# A2D_ascii.net
KiCad netlist of a schematic drawn in Altium Designer
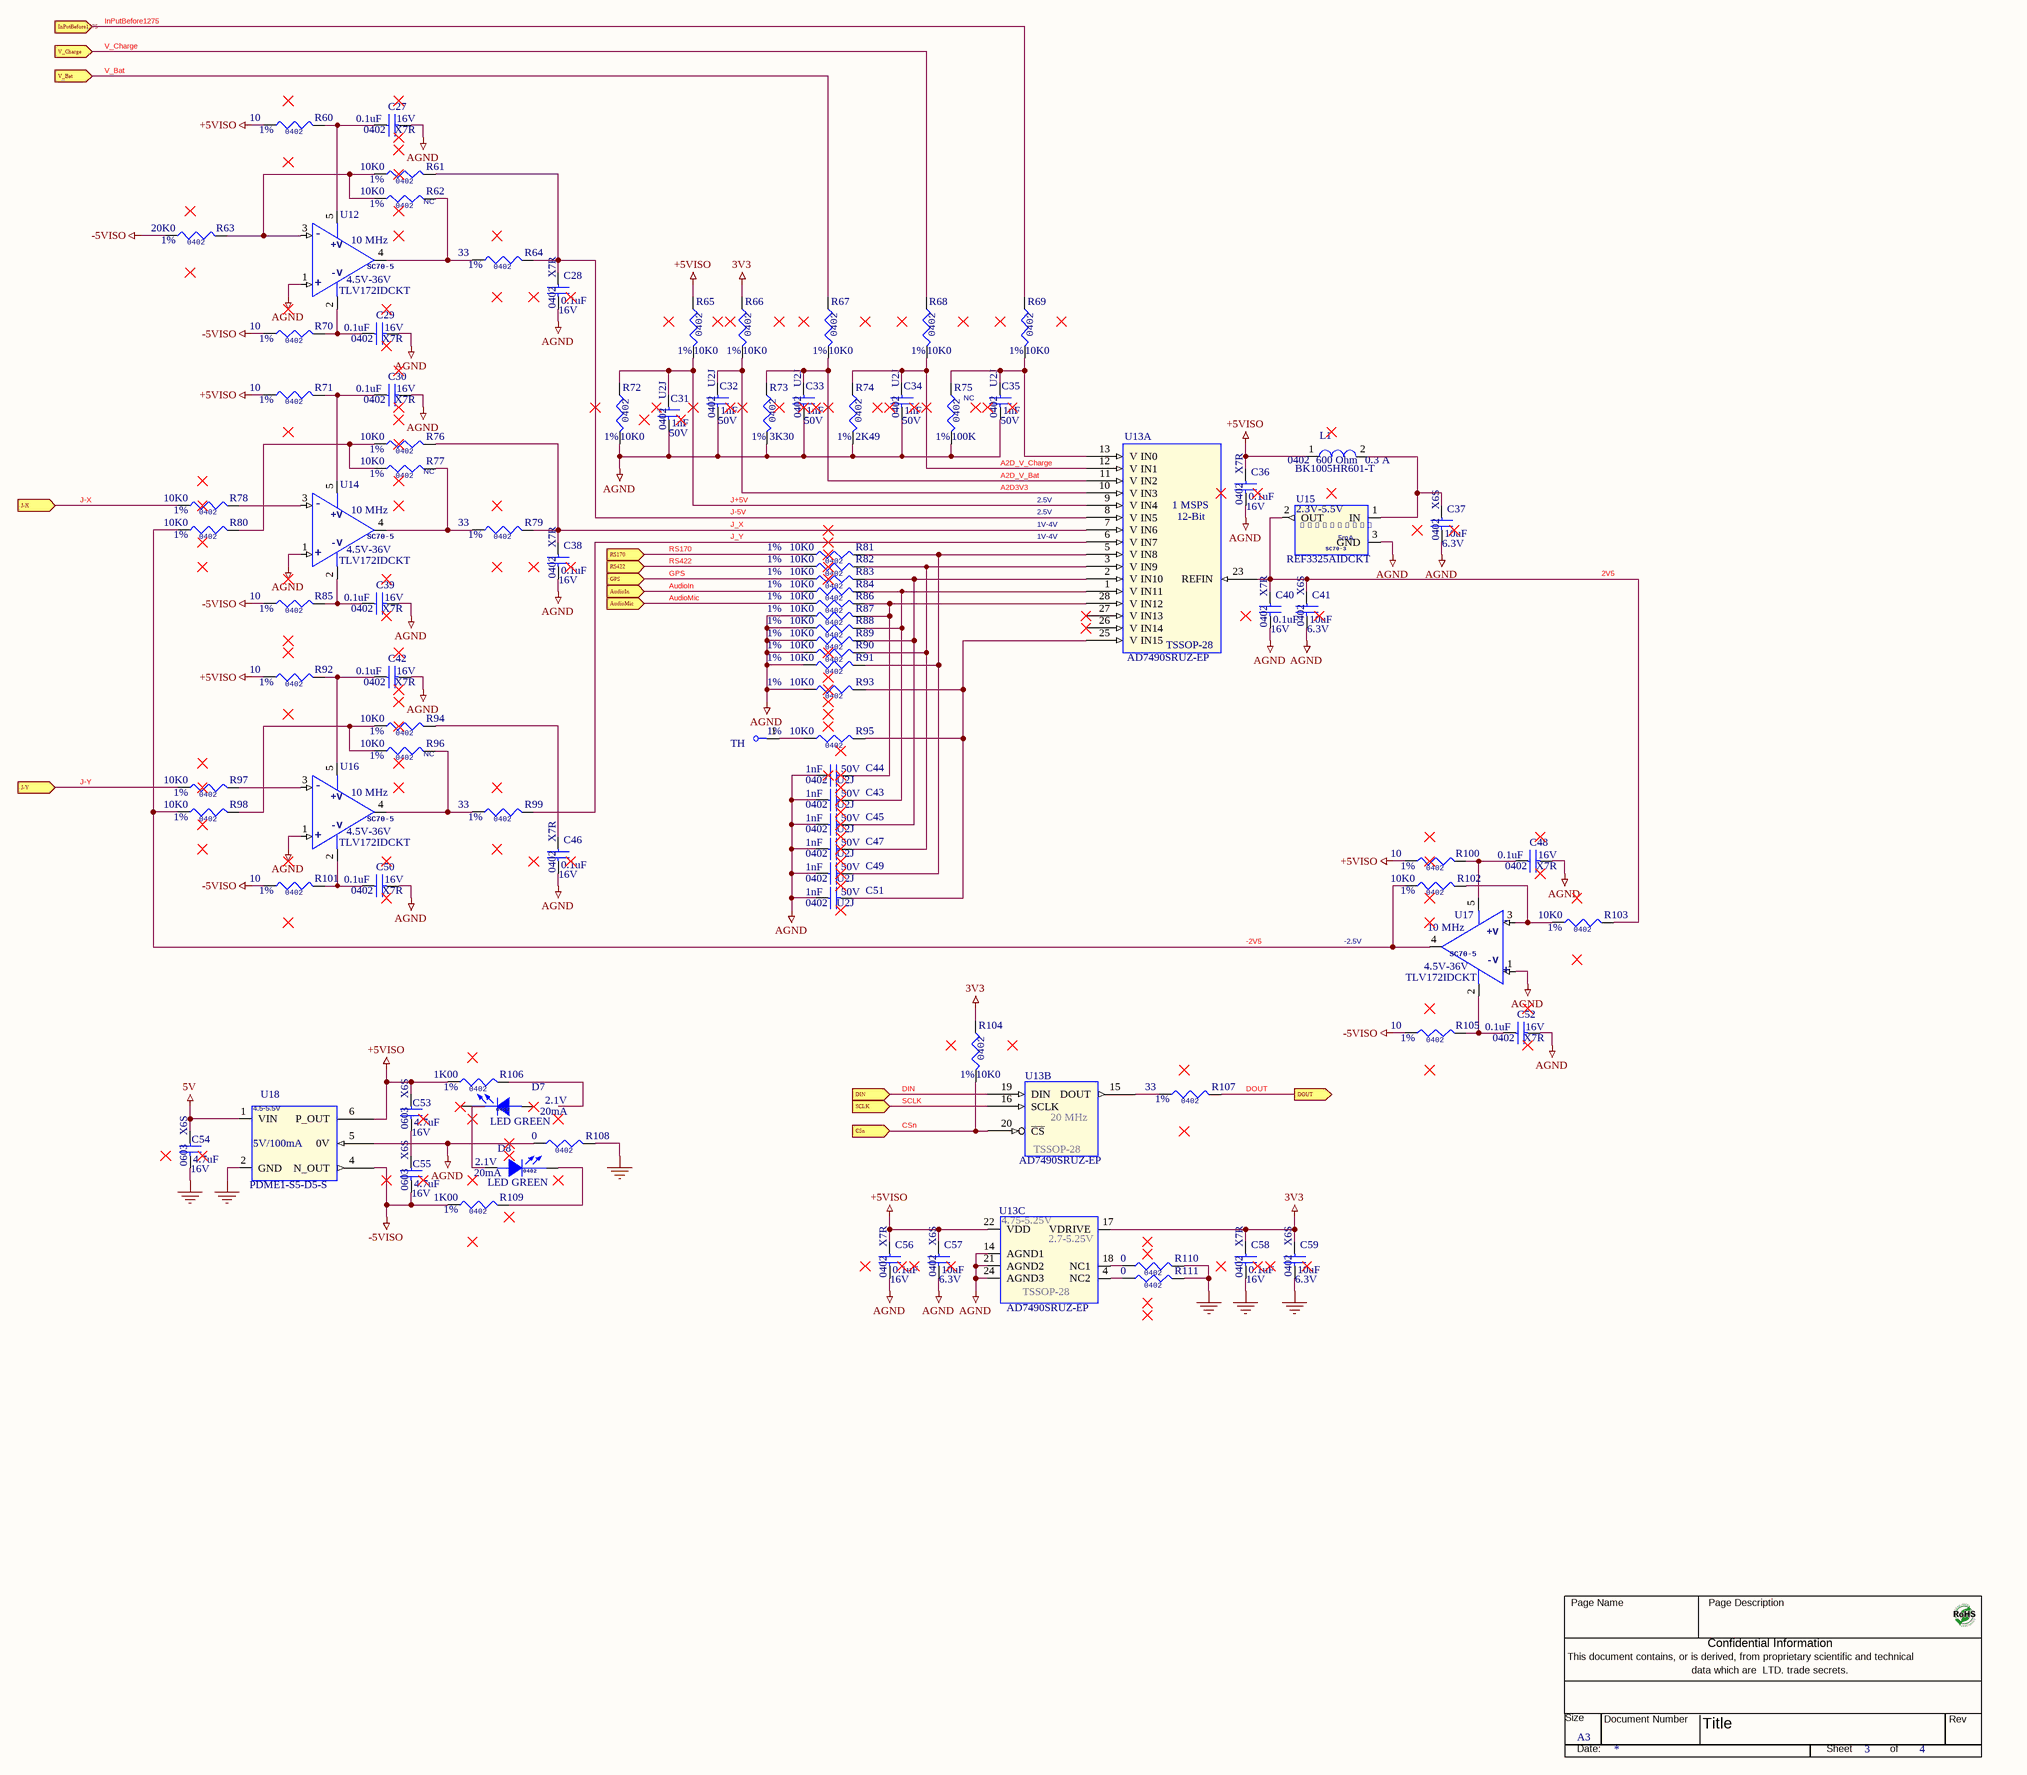
[diagram p0: A2D_ascii.SchDoc]

(export (version "E")
  (design (tool "Eeschema 10.0.6"))
  (components
    (comp (ref "*")
      (value "MobulusTitleBlockBlank")
      (fields
        (field (name "PAGE SIZE") "A3")
        (field (name "PAGE NUMBER") "3")
        (field (name "PAGE COUNT") "4")
      )
      (libsource (lib "*") (part "MobulusTitleBlockBlank"))
    )
    (comp (ref "C27")
      (value "0.1uF")
      (footprint "0402")
      (description "CAP_CER_0.1uF_16V_X7R_0402")
      (fields
        (field (name "VOLTAGE") "16V")
        (field (name "PART NUMBER") "CC0402KRX7R7BB104")
        (field (name "PCBFOOTPRINT") "0402   X7R")
        (field (name "MFG") "Yageo")
      )
      (libsource (lib "*") (part "CAP0402_0.1uF 16V"))
    )
    (comp (ref "C28")
      (value "0.1uF")
      (footprint "0402")
      (description "CAP_CER_0.1uF_16V_X7R_0402")
      (fields
        (field (name "VOLTAGE") "16V")
        (field (name "PART NUMBER") "CC0402KRX7R7BB104")
        (field (name "PCBFOOTPRINT") "0402   X7R")
        (field (name "MFG") "Yageo")
      )
      (libsource (lib "") (part "CAP0402_0.1uF 16V_1"))
    )
    (comp (ref "C29")
      (value "0.1uF")
      (footprint "0402")
      (description "CAP_CER_0.1uF_16V_X7R_0402")
      (fields
        (field (name "VOLTAGE") "16V")
        (field (name "PART NUMBER") "CC0402KRX7R7BB104")
        (field (name "PCBFOOTPRINT") "0402   X7R")
        (field (name "MFG") "Yageo")
      )
      (libsource (lib "*") (part "CAP0402_0.1uF 16V"))
    )
    (comp (ref "C30")
      (value "0.1uF")
      (footprint "0402")
      (description "CAP_CER_0.1uF_16V_X7R_0402")
      (fields
        (field (name "VOLTAGE") "16V")
        (field (name "PART NUMBER") "CC0402KRX7R7BB104")
        (field (name "PCBFOOTPRINT") "0402   X7R")
        (field (name "MFG") "Yageo")
      )
      (libsource (lib "*") (part "CAP0402_0.1uF 16V"))
    )
    (comp (ref "C31")
      (value "1nF")
      (footprint "0402")
      (description "CAP_CER_1nF_50V_0402_U2J")
      (fields
        (field (name "VOLTAGE") "50V")
        (field (name "PART NUMBER") "C0402C102J5JAC7867")
        (field (name "PCBFOOTPRINT") "0402   U2J")
        (field (name "MFG") "KEMET")
      )
      (libsource (lib "*") (part "CAP0402_1nF 50V"))
    )
    (comp (ref "C32")
      (value "1nF")
      (footprint "0402")
      (description "CAP_CER_1nF_50V_0402_U2J")
      (fields
        (field (name "VOLTAGE") "50V")
        (field (name "PART NUMBER") "C0402C102J5JAC7867")
        (field (name "PCBFOOTPRINT") "0402   U2J")
        (field (name "MFG") "KEMET")
      )
      (libsource (lib "*") (part "CAP0402_1nF 50V"))
    )
    (comp (ref "C33")
      (value "1nF")
      (footprint "0402")
      (description "CAP_CER_1nF_50V_0402_U2J")
      (fields
        (field (name "VOLTAGE") "50V")
        (field (name "PART NUMBER") "C0402C102J5JAC7867")
        (field (name "PCBFOOTPRINT") "0402   U2J")
        (field (name "MFG") "KEMET")
      )
      (libsource (lib "*") (part "CAP0402_1nF 50V"))
    )
    (comp (ref "C34")
      (value "1nF")
      (footprint "0402")
      (description "CAP_CER_1nF_50V_0402_U2J")
      (fields
        (field (name "VOLTAGE") "50V")
        (field (name "PART NUMBER") "C0402C102J5JAC7867")
        (field (name "PCBFOOTPRINT") "0402   U2J")
        (field (name "MFG") "KEMET")
      )
      (libsource (lib "*") (part "CAP0402_1nF 50V"))
    )
    (comp (ref "C35")
      (value "1nF")
      (footprint "0402")
      (description "CAP_CER_1nF_50V_0402_U2J")
      (fields
        (field (name "VOLTAGE") "50V")
        (field (name "PART NUMBER") "C0402C102J5JAC7867")
        (field (name "PCBFOOTPRINT") "0402   U2J")
        (field (name "MFG") "KEMET")
      )
      (libsource (lib "*") (part "CAP0402_1nF 50V"))
    )
    (comp (ref "C36")
      (value "0.1uF")
      (footprint "0402")
      (description "CAP_CER_0.1uF_16V_X7R_0402")
      (fields
        (field (name "VOLTAGE") "16V")
        (field (name "PART NUMBER") "CC0402KRX7R7BB104")
        (field (name "PCBFOOTPRINT") "0402   X7R")
        (field (name "MFG") "Yageo")
      )
      (libsource (lib "") (part "CAP0402_0.1uF 16V_1"))
    )
    (comp (ref "C37")
      (value "10uF")
      (footprint "0402")
      (description "CAP CER 10UF 6.3V X6S 0402")
      (fields
        (field (name "VOLTAGE") "6.3V")
        (field (name "PART NUMBER") "GRM155C80J106ME11J")
        (field (name "PCBFOOTPRINT") "0402   X6S")
        (field (name "MFG") "Murata Electronics")
      )
      (libsource (lib "*") (part "CAP0402_10uF 6.3V"))
    )
    (comp (ref "C38")
      (value "0.1uF")
      (footprint "0402")
      (description "CAP_CER_0.1uF_16V_X7R_0402")
      (fields
        (field (name "VOLTAGE") "16V")
        (field (name "PART NUMBER") "CC0402KRX7R7BB104")
        (field (name "PCBFOOTPRINT") "0402   X7R")
        (field (name "MFG") "Yageo")
      )
      (libsource (lib "") (part "CAP0402_0.1uF 16V_1"))
    )
    (comp (ref "C39")
      (value "0.1uF")
      (footprint "0402")
      (description "CAP_CER_0.1uF_16V_X7R_0402")
      (fields
        (field (name "VOLTAGE") "16V")
        (field (name "PART NUMBER") "CC0402KRX7R7BB104")
        (field (name "PCBFOOTPRINT") "0402   X7R")
        (field (name "MFG") "Yageo")
      )
      (libsource (lib "*") (part "CAP0402_0.1uF 16V"))
    )
    (comp (ref "C40")
      (value "0.1uF")
      (footprint "0402")
      (description "CAP_CER_0.1uF_16V_X7R_0402")
      (fields
        (field (name "VOLTAGE") "16V")
        (field (name "PART NUMBER") "CC0402KRX7R7BB104")
        (field (name "PCBFOOTPRINT") "0402   X7R")
        (field (name "MFG") "Yageo")
      )
      (libsource (lib "") (part "CAP0402_0.1uF 16V_1"))
    )
    (comp (ref "C41")
      (value "10uF")
      (footprint "0402")
      (description "CAP CER 10UF 6.3V X6S 0402")
      (fields
        (field (name "VOLTAGE") "6.3V")
        (field (name "PART NUMBER") "GRM155C80J106ME11J")
        (field (name "PCBFOOTPRINT") "0402   X6S")
        (field (name "MFG") "Murata Electronics")
      )
      (libsource (lib "*") (part "CAP0402_10uF 6.3V"))
    )
    (comp (ref "C42")
      (value "0.1uF")
      (footprint "0402")
      (description "CAP_CER_0.1uF_16V_X7R_0402")
      (fields
        (field (name "VOLTAGE") "16V")
        (field (name "PART NUMBER") "CC0402KRX7R7BB104")
        (field (name "PCBFOOTPRINT") "0402   X7R")
        (field (name "MFG") "Yageo")
      )
      (libsource (lib "*") (part "CAP0402_0.1uF 16V"))
    )
    (comp (ref "C43")
      (value "1nF")
      (footprint "0402")
      (description "CAP_CER_1nF_50V_0402_U2J")
      (fields
        (field (name "VOLTAGE") "50V")
        (field (name "PART NUMBER") "C0402C102J5JAC7867")
        (field (name "PCBFOOTPRINT") "0402   U2J")
        (field (name "MFG") "KEMET")
      )
      (libsource (lib "") (part "CAP0402_1nF 50V_1"))
    )
    (comp (ref "C44")
      (value "1nF")
      (footprint "0402")
      (description "CAP_CER_1nF_50V_0402_U2J")
      (fields
        (field (name "VOLTAGE") "50V")
        (field (name "PART NUMBER") "C0402C102J5JAC7867")
        (field (name "PCBFOOTPRINT") "0402   U2J")
        (field (name "MFG") "KEMET")
      )
      (libsource (lib "") (part "CAP0402_1nF 50V_1"))
    )
    (comp (ref "C45")
      (value "1nF")
      (footprint "0402")
      (description "CAP_CER_1nF_50V_0402_U2J")
      (fields
        (field (name "VOLTAGE") "50V")
        (field (name "PART NUMBER") "C0402C102J5JAC7867")
        (field (name "PCBFOOTPRINT") "0402   U2J")
        (field (name "MFG") "KEMET")
      )
      (libsource (lib "") (part "CAP0402_1nF 50V_1"))
    )
    (comp (ref "C46")
      (value "0.1uF")
      (footprint "0402")
      (description "CAP_CER_0.1uF_16V_X7R_0402")
      (fields
        (field (name "VOLTAGE") "16V")
        (field (name "PART NUMBER") "CC0402KRX7R7BB104")
        (field (name "PCBFOOTPRINT") "0402   X7R")
        (field (name "MFG") "Yageo")
      )
      (libsource (lib "") (part "CAP0402_0.1uF 16V_1"))
    )
    (comp (ref "C47")
      (value "1nF")
      (footprint "0402")
      (description "CAP_CER_1nF_50V_0402_U2J")
      (fields
        (field (name "VOLTAGE") "50V")
        (field (name "PART NUMBER") "C0402C102J5JAC7867")
        (field (name "PCBFOOTPRINT") "0402   U2J")
        (field (name "MFG") "KEMET")
      )
      (libsource (lib "") (part "CAP0402_1nF 50V_1"))
    )
    (comp (ref "C48")
      (value "0.1uF")
      (footprint "0402")
      (description "CAP_CER_0.1uF_16V_X7R_0402")
      (fields
        (field (name "VOLTAGE") "16V")
        (field (name "PART NUMBER") "CC0402KRX7R7BB104")
        (field (name "PCBFOOTPRINT") "0402   X7R")
        (field (name "MFG") "Yageo")
      )
      (libsource (lib "*") (part "CAP0402_0.1uF 16V"))
    )
    (comp (ref "C49")
      (value "1nF")
      (footprint "0402")
      (description "CAP_CER_1nF_50V_0402_U2J")
      (fields
        (field (name "VOLTAGE") "50V")
        (field (name "PART NUMBER") "C0402C102J5JAC7867")
        (field (name "PCBFOOTPRINT") "0402   U2J")
        (field (name "MFG") "KEMET")
      )
      (libsource (lib "") (part "CAP0402_1nF 50V_1"))
    )
    (comp (ref "C50")
      (value "0.1uF")
      (footprint "0402")
      (description "CAP_CER_0.1uF_16V_X7R_0402")
      (fields
        (field (name "VOLTAGE") "16V")
        (field (name "PART NUMBER") "CC0402KRX7R7BB104")
        (field (name "PCBFOOTPRINT") "0402   X7R")
        (field (name "MFG") "Yageo")
      )
      (libsource (lib "*") (part "CAP0402_0.1uF 16V"))
    )
    (comp (ref "C51")
      (value "1nF")
      (footprint "0402")
      (description "CAP_CER_1nF_50V_0402_U2J")
      (fields
        (field (name "VOLTAGE") "50V")
        (field (name "PART NUMBER") "C0402C102J5JAC7867")
        (field (name "PCBFOOTPRINT") "0402   U2J")
        (field (name "MFG") "KEMET")
      )
      (libsource (lib "") (part "CAP0402_1nF 50V_1"))
    )
    (comp (ref "C52")
      (value "0.1uF")
      (footprint "0402")
      (description "CAP_CER_0.1uF_16V_X7R_0402")
      (fields
        (field (name "VOLTAGE") "16V")
        (field (name "PART NUMBER") "CC0402KRX7R7BB104")
        (field (name "PCBFOOTPRINT") "0402   X7R")
        (field (name "MFG") "Yageo")
      )
      (libsource (lib "*") (part "CAP0402_0.1uF 16V"))
    )
    (comp (ref "C53")
      (value "4.7uF")
      (footprint "0603")
      (description "CAP_CER_4.7UF_16V_X6S_0603")
      (fields
        (field (name "VOLTAGE") "16V")
        (field (name "PART NUMBER") "C1608X6S1C475M080AC")
        (field (name "PCBFOOTPRINT") "0603   X6S")
        (field (name "MFG") "TDK Corporation")
      )
      (libsource (lib "*") (part "CAP0603_4.7uF 16V"))
    )
    (comp (ref "C54")
      (value "4.7uF")
      (footprint "0603")
      (description "CAP_CER_4.7UF_16V_X6S_0603")
      (fields
        (field (name "VOLTAGE") "16V")
        (field (name "PART NUMBER") "C1608X6S1C475M080AC")
        (field (name "PCBFOOTPRINT") "0603   X6S")
        (field (name "MFG") "TDK Corporation")
      )
      (libsource (lib "*") (part "CAP0603_4.7uF 16V"))
    )
    (comp (ref "C55")
      (value "4.7uF")
      (footprint "0603")
      (description "CAP_CER_4.7UF_16V_X6S_0603")
      (fields
        (field (name "VOLTAGE") "16V")
        (field (name "PART NUMBER") "C1608X6S1C475M080AC")
        (field (name "PCBFOOTPRINT") "0603   X6S")
        (field (name "MFG") "TDK Corporation")
      )
      (libsource (lib "*") (part "CAP0603_4.7uF 16V"))
    )
    (comp (ref "C56")
      (value "0.1uF")
      (footprint "0402")
      (description "CAP_CER_0.1uF_16V_X7R_0402")
      (fields
        (field (name "VOLTAGE") "16V")
        (field (name "PART NUMBER") "CC0402KRX7R7BB104")
        (field (name "PCBFOOTPRINT") "0402   X7R")
        (field (name "MFG") "Yageo")
      )
      (libsource (lib "") (part "CAP0402_0.1uF 16V_1"))
    )
    (comp (ref "C57")
      (value "10uF")
      (footprint "0402")
      (description "CAP CER 10UF 6.3V X6S 0402")
      (fields
        (field (name "VOLTAGE") "6.3V")
        (field (name "PART NUMBER") "GRM155C80J106ME11J")
        (field (name "PCBFOOTPRINT") "0402   X6S")
        (field (name "MFG") "Murata Electronics")
      )
      (libsource (lib "*") (part "CAP0402_10uF 6.3V"))
    )
    (comp (ref "C58")
      (value "0.1uF")
      (footprint "0402")
      (description "CAP_CER_0.1uF_16V_X7R_0402")
      (fields
        (field (name "VOLTAGE") "16V")
        (field (name "PART NUMBER") "CC0402KRX7R7BB104")
        (field (name "PCBFOOTPRINT") "0402   X7R")
        (field (name "MFG") "Yageo")
      )
      (libsource (lib "") (part "CAP0402_0.1uF 16V_1"))
    )
    (comp (ref "C59")
      (value "10uF")
      (footprint "0402")
      (description "CAP CER 10UF 6.3V X6S 0402")
      (fields
        (field (name "VOLTAGE") "6.3V")
        (field (name "PART NUMBER") "GRM155C80J106ME11J")
        (field (name "PCBFOOTPRINT") "0402   X6S")
        (field (name "MFG") "Murata Electronics")
      )
      (libsource (lib "*") (part "CAP0402_10uF 6.3V"))
    )
    (comp (ref "D7")
      (value "LED GREEN")
      (footprint "LED_0402")
      (description "LED GREEN CLEAR CHIP SMD")
      (fields
        (field (name "VOLTAGE") "2.1V")
        (field (name "PART NUMBER") "XZVG68W-2")
        (field (name "MFG") "SunLED")
        (field (name "CURRENT") "20mA")
      )
      (libsource (lib "*") (part "LED_0402_GREEN"))
    )
    (comp (ref "D8")
      (value "LED GREEN")
      (footprint "LED_0402")
      (description "LED GREEN CLEAR CHIP SMD")
      (fields
        (field (name "VOLTAGE") "2.1V")
        (field (name "PART NUMBER") "XZVG68W-2")
        (field (name "MFG") "SunLED")
        (field (name "CURRENT") "20mA")
      )
      (libsource (lib "*") (part "LED_0402_GREEN"))
    )
    (comp (ref "ICT1") (value "TH") (footprint "ICT") (libsource (lib "*") (part "ICT")))
    (comp (ref "L1")
      (value "BK1005HR601-T")
      (footprint "L0402")
      (description "FERRITE BEAD 600 OHM 0402 1LN")
      (fields
        (field (name "IMPEDANCE") "600 Ohm")
        (field (name "PCBFOOTPRINT") "0402")
        (field (name "MFG") "Taiyo Yuden")
        (field (name "CURRENT") "0.3 A")
      )
      (libsource (lib "*") (part "BK1005HR601-T 600 0.3A"))
    )
    (comp (ref "R60")
      (value "10")
      (footprint "0402")
      (description "RES SMD 10 OHM 1% 1/16W 0402")
      (fields
        (field (name "TOLERANCE") "1%")
        (field (name "POWER") "1/16W")
        (field (name "PART NUMBER") "RC0402FR-0710RL")
      )
      (libsource (lib "*") (part "R0402_10R_1%"))
    )
    (comp (ref "R61")
      (value "10K0")
      (footprint "0402")
      (description "RES SMD 10K OHM 1% 1/16W 0402")
      (fields
        (field (name "TOLERANCE") "1%")
        (field (name "POWER") "1/16W")
        (field (name "PART NUMBER") "RC0402FR-0710KL")
      )
      (libsource (lib "*") (part "R0402_10K0_1%"))
    )
    (comp (ref "R62")
      (value "10K0")
      (footprint "0402")
      (description "RES SMD 10K OHM 1% 1/16W 0402")
      (fields
        (field (name "TOLERANCE") "1%")
        (field (name "POWER") "1/16W")
        (field (name "PART NUMBER") "RC0402FR-0710KL")
        (field (name "ASSY") "NC")
      )
      (libsource (lib "*") (part "R0402_10K0_1%"))
    )
    (comp (ref "R63")
      (value "20K0")
      (footprint "0402")
      (description "RES SMD 20K OHM 1% 1/16W 0402")
      (fields
        (field (name "TOLERANCE") "1%")
        (field (name "POWER") "1/16W")
        (field (name "PART NUMBER") "RC0402FR-0720KL")
      )
      (libsource (lib "*") (part "R0402_20K0_1%"))
    )
    (comp (ref "R64")
      (value "33")
      (footprint "0402")
      (description "RES 33R 1% 1/5W 0402")
      (fields
        (field (name "TOLERANCE") "1%")
        (field (name "POWER") "1/16W")
        (field (name "PART NUMBER") "RCS040233R0FKED")
      )
      (libsource (lib "*") (part "R0402_33R_1%"))
    )
    (comp (ref "R65")
      (value "10K0")
      (footprint "0402")
      (description "RES SMD 10K OHM 1% 1/16W 0402")
      (fields
        (field (name "TOLERANCE") "1%")
        (field (name "POWER") "1/16W")
        (field (name "PART NUMBER") "RC0402FR-0710KL")
      )
      (libsource (lib "") (part "R0402_10K0_1%_1"))
    )
    (comp (ref "R66")
      (value "10K0")
      (footprint "0402")
      (description "RES SMD 10K OHM 1% 1/16W 0402")
      (fields
        (field (name "TOLERANCE") "1%")
        (field (name "POWER") "1/16W")
        (field (name "PART NUMBER") "RC0402FR-0710KL")
      )
      (libsource (lib "") (part "R0402_10K0_1%_1"))
    )
    (comp (ref "R67")
      (value "10K0")
      (footprint "0402")
      (description "RES SMD 10K OHM 1% 1/16W 0402")
      (fields
        (field (name "TOLERANCE") "1%")
        (field (name "POWER") "1/16W")
        (field (name "PART NUMBER") "RC0402FR-0710KL")
      )
      (libsource (lib "") (part "R0402_10K0_1%_1"))
    )
    (comp (ref "R68")
      (value "10K0")
      (footprint "0402")
      (description "RES SMD 10K OHM 1% 1/16W 0402")
      (fields
        (field (name "TOLERANCE") "1%")
        (field (name "POWER") "1/16W")
        (field (name "PART NUMBER") "RC0402FR-0710KL")
      )
      (libsource (lib "") (part "R0402_10K0_1%_1"))
    )
    (comp (ref "R69")
      (value "10K0")
      (footprint "0402")
      (description "RES SMD 10K OHM 1% 1/16W 0402")
      (fields
        (field (name "TOLERANCE") "1%")
        (field (name "POWER") "1/16W")
        (field (name "PART NUMBER") "RC0402FR-0710KL")
      )
      (libsource (lib "") (part "R0402_10K0_1%_1"))
    )
    (comp (ref "R70")
      (value "10")
      (footprint "0402")
      (description "RES SMD 10 OHM 1% 1/16W 0402")
      (fields
        (field (name "TOLERANCE") "1%")
        (field (name "POWER") "1/16W")
        (field (name "PART NUMBER") "RC0402FR-0710RL")
      )
      (libsource (lib "*") (part "R0402_10R_1%"))
    )
    (comp (ref "R71")
      (value "10")
      (footprint "0402")
      (description "RES SMD 10 OHM 1% 1/16W 0402")
      (fields
        (field (name "TOLERANCE") "1%")
        (field (name "POWER") "1/16W")
        (field (name "PART NUMBER") "RC0402FR-0710RL")
      )
      (libsource (lib "*") (part "R0402_10R_1%"))
    )
    (comp (ref "R72")
      (value "10K0")
      (footprint "0402")
      (description "RES SMD 10K OHM 1% 1/16W 0402")
      (fields
        (field (name "TOLERANCE") "1%")
        (field (name "POWER") "1/16W")
        (field (name "PART NUMBER") "RC0402FR-0710KL")
      )
      (libsource (lib "") (part "R0402_10K0_1%_1"))
    )
    (comp (ref "R73")
      (value "3K30")
      (footprint "0402")
      (description "RES 3K3 1% 1/16W 0402")
      (fields
        (field (name "TOLERANCE") "1%")
        (field (name "POWER") "1/16W")
        (field (name "PART NUMBER") "RT0402FRE073K3L")
      )
      (libsource (lib "*") (part "R0402_3K30_1%"))
    )
    (comp (ref "R74")
      (value "2K49")
      (footprint "0402")
      (description "RES 2K49 1% 1/16W 0402")
      (fields
        (field (name "TOLERANCE") "1%")
        (field (name "POWER") "1/16W")
        (field (name "PART NUMBER") "RC0402FR-072K49L")
      )
      (libsource (lib "*") (part "R0402_2K49_1%"))
    )
    (comp (ref "R75")
      (value "100K")
      (footprint "0402")
      (description "RES SMD 100K OHM 1% 1/16W 0402")
      (fields
        (field (name "TOLERANCE") "1%")
        (field (name "POWER") "1/16W")
        (field (name "PART NUMBER") "RC0402FR-07100KL")
        (field (name "ASSY") "NC")
      )
      (libsource (lib "*") (part "R0402_100K_1%"))
    )
    (comp (ref "R76")
      (value "10K0")
      (footprint "0402")
      (description "RES SMD 10K OHM 1% 1/16W 0402")
      (fields
        (field (name "TOLERANCE") "1%")
        (field (name "POWER") "1/16W")
        (field (name "PART NUMBER") "RC0402FR-0710KL")
      )
      (libsource (lib "*") (part "R0402_10K0_1%"))
    )
    (comp (ref "R77")
      (value "10K0")
      (footprint "0402")
      (description "RES SMD 10K OHM 1% 1/16W 0402")
      (fields
        (field (name "TOLERANCE") "1%")
        (field (name "POWER") "1/16W")
        (field (name "PART NUMBER") "RC0402FR-0710KL")
        (field (name "ASSY") "NC")
      )
      (libsource (lib "*") (part "R0402_10K0_1%"))
    )
    (comp (ref "R78")
      (value "10K0")
      (footprint "0402")
      (description "RES SMD 10K OHM 1% 1/16W 0402")
      (fields
        (field (name "TOLERANCE") "1%")
        (field (name "POWER") "1/16W")
        (field (name "PART NUMBER") "RC0402FR-0710KL")
      )
      (libsource (lib "*") (part "R0402_10K0_1%"))
    )
    (comp (ref "R79")
      (value "33")
      (footprint "0402")
      (description "RES 33R 1% 1/5W 0402")
      (fields
        (field (name "TOLERANCE") "1%")
        (field (name "POWER") "1/16W")
        (field (name "PART NUMBER") "RCS040233R0FKED")
      )
      (libsource (lib "*") (part "R0402_33R_1%"))
    )
    (comp (ref "R80")
      (value "10K0")
      (footprint "0402")
      (description "RES SMD 10K OHM 1% 1/16W 0402")
      (fields
        (field (name "TOLERANCE") "1%")
        (field (name "POWER") "1/16W")
        (field (name "PART NUMBER") "RC0402FR-0710KL")
      )
      (libsource (lib "*") (part "R0402_10K0_1%"))
    )
    (comp (ref "R81")
      (value "10K0")
      (footprint "0402")
      (description "RES SMD 10K OHM 1% 1/16W 0402")
      (fields
        (field (name "TOLERANCE") "1%")
        (field (name "POWER") "1/16W")
        (field (name "PART NUMBER") "RC0402FR-0710KL")
      )
      (libsource (lib "*") (part "R0402_10K0_1%"))
    )
    (comp (ref "R82")
      (value "10K0")
      (footprint "0402")
      (description "RES SMD 10K OHM 1% 1/16W 0402")
      (fields
        (field (name "TOLERANCE") "1%")
        (field (name "POWER") "1/16W")
        (field (name "PART NUMBER") "RC0402FR-0710KL")
      )
      (libsource (lib "*") (part "R0402_10K0_1%"))
    )
    (comp (ref "R83")
      (value "10K0")
      (footprint "0402")
      (description "RES SMD 10K OHM 1% 1/16W 0402")
      (fields
        (field (name "TOLERANCE") "1%")
        (field (name "POWER") "1/16W")
        (field (name "PART NUMBER") "RC0402FR-0710KL")
      )
      (libsource (lib "*") (part "R0402_10K0_1%"))
    )
    (comp (ref "R84")
      (value "10K0")
      (footprint "0402")
      (description "RES SMD 10K OHM 1% 1/16W 0402")
      (fields
        (field (name "TOLERANCE") "1%")
        (field (name "POWER") "1/16W")
        (field (name "PART NUMBER") "RC0402FR-0710KL")
      )
      (libsource (lib "*") (part "R0402_10K0_1%"))
    )
    (comp (ref "R85")
      (value "10")
      (footprint "0402")
      (description "RES SMD 10 OHM 1% 1/16W 0402")
      (fields
        (field (name "TOLERANCE") "1%")
        (field (name "POWER") "1/16W")
        (field (name "PART NUMBER") "RC0402FR-0710RL")
      )
      (libsource (lib "*") (part "R0402_10R_1%"))
    )
    (comp (ref "R86")
      (value "10K0")
      (footprint "0402")
      (description "RES SMD 10K OHM 1% 1/16W 0402")
      (fields
        (field (name "TOLERANCE") "1%")
        (field (name "POWER") "1/16W")
        (field (name "PART NUMBER") "RC0402FR-0710KL")
      )
      (libsource (lib "*") (part "R0402_10K0_1%"))
    )
    (comp (ref "R87")
      (value "10K0")
      (footprint "0402")
      (description "RES SMD 10K OHM 1% 1/16W 0402")
      (fields
        (field (name "TOLERANCE") "1%")
        (field (name "POWER") "1/16W")
        (field (name "PART NUMBER") "RC0402FR-0710KL")
      )
      (libsource (lib "*") (part "R0402_10K0_1%"))
    )
    (comp (ref "R88")
      (value "10K0")
      (footprint "0402")
      (description "RES SMD 10K OHM 1% 1/16W 0402")
      (fields
        (field (name "TOLERANCE") "1%")
        (field (name "POWER") "1/16W")
        (field (name "PART NUMBER") "RC0402FR-0710KL")
      )
      (libsource (lib "*") (part "R0402_10K0_1%"))
    )
    (comp (ref "R89")
      (value "10K0")
      (footprint "0402")
      (description "RES SMD 10K OHM 1% 1/16W 0402")
      (fields
        (field (name "TOLERANCE") "1%")
        (field (name "POWER") "1/16W")
        (field (name "PART NUMBER") "RC0402FR-0710KL")
      )
      (libsource (lib "*") (part "R0402_10K0_1%"))
    )
    (comp (ref "R90")
      (value "10K0")
      (footprint "0402")
      (description "RES SMD 10K OHM 1% 1/16W 0402")
      (fields
        (field (name "TOLERANCE") "1%")
        (field (name "POWER") "1/16W")
        (field (name "PART NUMBER") "RC0402FR-0710KL")
      )
      (libsource (lib "*") (part "R0402_10K0_1%"))
    )
    (comp (ref "R91")
      (value "10K0")
      (footprint "0402")
      (description "RES SMD 10K OHM 1% 1/16W 0402")
      (fields
        (field (name "TOLERANCE") "1%")
        (field (name "POWER") "1/16W")
        (field (name "PART NUMBER") "RC0402FR-0710KL")
      )
      (libsource (lib "*") (part "R0402_10K0_1%"))
    )
    (comp (ref "R92")
      (value "10")
      (footprint "0402")
      (description "RES SMD 10 OHM 1% 1/16W 0402")
      (fields
        (field (name "TOLERANCE") "1%")
        (field (name "POWER") "1/16W")
        (field (name "PART NUMBER") "RC0402FR-0710RL")
      )
      (libsource (lib "*") (part "R0402_10R_1%"))
    )
    (comp (ref "R93")
      (value "10K0")
      (footprint "0402")
      (description "RES SMD 10K OHM 1% 1/16W 0402")
      (fields
        (field (name "TOLERANCE") "1%")
        (field (name "POWER") "1/16W")
        (field (name "PART NUMBER") "RC0402FR-0710KL")
      )
      (libsource (lib "*") (part "R0402_10K0_1%"))
    )
    (comp (ref "R94")
      (value "10K0")
      (footprint "0402")
      (description "RES SMD 10K OHM 1% 1/16W 0402")
      (fields
        (field (name "TOLERANCE") "1%")
        (field (name "POWER") "1/16W")
        (field (name "PART NUMBER") "RC0402FR-0710KL")
      )
      (libsource (lib "*") (part "R0402_10K0_1%"))
    )
    (comp (ref "R95")
      (value "10K0")
      (footprint "0402")
      (description "RES SMD 10K OHM 1% 1/16W 0402")
      (fields
        (field (name "TOLERANCE") "1%")
        (field (name "POWER") "1/16W")
        (field (name "PART NUMBER") "RC0402FR-0710KL")
      )
      (libsource (lib "*") (part "R0402_10K0_1%"))
    )
    (comp (ref "R96")
      (value "10K0")
      (footprint "0402")
      (description "RES SMD 10K OHM 1% 1/16W 0402")
      (fields
        (field (name "TOLERANCE") "1%")
        (field (name "POWER") "1/16W")
        (field (name "PART NUMBER") "RC0402FR-0710KL")
        (field (name "ASSY") "NC")
      )
      (libsource (lib "*") (part "R0402_10K0_1%"))
    )
    (comp (ref "R97")
      (value "10K0")
      (footprint "0402")
      (description "RES SMD 10K OHM 1% 1/16W 0402")
      (fields
        (field (name "TOLERANCE") "1%")
        (field (name "POWER") "1/16W")
        (field (name "PART NUMBER") "RC0402FR-0710KL")
      )
      (libsource (lib "*") (part "R0402_10K0_1%"))
    )
    (comp (ref "R98")
      (value "10K0")
      (footprint "0402")
      (description "RES SMD 10K OHM 1% 1/16W 0402")
      (fields
        (field (name "TOLERANCE") "1%")
        (field (name "POWER") "1/16W")
        (field (name "PART NUMBER") "RC0402FR-0710KL")
      )
      (libsource (lib "*") (part "R0402_10K0_1%"))
    )
    (comp (ref "R99")
      (value "33")
      (footprint "0402")
      (description "RES 33R 1% 1/5W 0402")
      (fields
        (field (name "TOLERANCE") "1%")
        (field (name "POWER") "1/16W")
        (field (name "PART NUMBER") "RCS040233R0FKED")
      )
      (libsource (lib "*") (part "R0402_33R_1%"))
    )
    (comp (ref "R100")
      (value "10")
      (footprint "0402")
      (description "RES SMD 10 OHM 1% 1/16W 0402")
      (fields
        (field (name "TOLERANCE") "1%")
        (field (name "POWER") "1/16W")
        (field (name "PART NUMBER") "RC0402FR-0710RL")
      )
      (libsource (lib "*") (part "R0402_10R_1%"))
    )
    (comp (ref "R101")
      (value "10")
      (footprint "0402")
      (description "RES SMD 10 OHM 1% 1/16W 0402")
      (fields
        (field (name "TOLERANCE") "1%")
        (field (name "POWER") "1/16W")
        (field (name "PART NUMBER") "RC0402FR-0710RL")
      )
      (libsource (lib "*") (part "R0402_10R_1%"))
    )
    (comp (ref "R102")
      (value "10K0")
      (footprint "0402")
      (description "RES SMD 10K OHM 1% 1/16W 0402")
      (fields
        (field (name "TOLERANCE") "1%")
        (field (name "POWER") "1/16W")
        (field (name "PART NUMBER") "RC0402FR-0710KL")
      )
      (libsource (lib "*") (part "R0402_10K0_1%"))
    )
    (comp (ref "R103")
      (value "10K0")
      (footprint "0402")
      (description "RES SMD 10K OHM 1% 1/16W 0402")
      (fields
        (field (name "TOLERANCE") "1%")
        (field (name "POWER") "1/16W")
        (field (name "PART NUMBER") "RC0402FR-0710KL")
      )
      (libsource (lib "*") (part "R0402_10K0_1%"))
    )
    (comp (ref "R104")
      (value "10K0")
      (footprint "0402")
      (description "RES SMD 10K OHM 1% 1/16W 0402")
      (fields
        (field (name "TOLERANCE") "1%")
        (field (name "POWER") "1/16W")
        (field (name "PART NUMBER") "RC0402FR-0710KL")
      )
      (libsource (lib "") (part "R0402_10K0_1%_1"))
    )
    (comp (ref "R105")
      (value "10")
      (footprint "0402")
      (description "RES SMD 10 OHM 1% 1/16W 0402")
      (fields
        (field (name "TOLERANCE") "1%")
        (field (name "POWER") "1/16W")
        (field (name "PART NUMBER") "RC0402FR-0710RL")
      )
      (libsource (lib "*") (part "R0402_10R_1%"))
    )
    (comp (ref "R106")
      (value "1K00")
      (footprint "0402")
      (description "RES SMD 1K OHM 1% 1/16W 0402")
      (fields
        (field (name "TOLERANCE") "1%")
        (field (name "POWER") "1/16W")
        (field (name "PART NUMBER") "RC0402FR-071KL")
      )
      (libsource (lib "*") (part "R0402_1K00_1%"))
    )
    (comp (ref "R107")
      (value "33")
      (footprint "0402")
      (description "RES 33R 1% 1/5W 0402")
      (fields
        (field (name "TOLERANCE") "1%")
        (field (name "POWER") "1/16W")
        (field (name "PART NUMBER") "RCS040233R0FKED")
      )
      (libsource (lib "*") (part "R0402_33R_1%"))
    )
    (comp (ref "R108")
      (value "0")
      (footprint "0402")
      (description "RES SMD 0 OHM JUMPER 1/16W 0402")
      (fields (field (name "POWER") "1/16W") (field (name "PART NUMBER") "RC0402JR-070RL"))
      (libsource (lib "*") (part "R0402_0R_5%"))
    )
    (comp (ref "R109")
      (value "1K00")
      (footprint "0402")
      (description "RES SMD 1K OHM 1% 1/16W 0402")
      (fields
        (field (name "TOLERANCE") "1%")
        (field (name "POWER") "1/16W")
        (field (name "PART NUMBER") "RC0402FR-071KL")
      )
      (libsource (lib "*") (part "R0402_1K00_1%"))
    )
    (comp (ref "R110")
      (value "0")
      (footprint "0402")
      (description "RES SMD 0 OHM JUMPER 1/16W 0402")
      (fields (field (name "POWER") "1/16W") (field (name "PART NUMBER") "RC0402JR-070RL"))
      (libsource (lib "*") (part "R0402_0R_5%"))
    )
    (comp (ref "R111")
      (value "0")
      (footprint "0402")
      (description "RES SMD 0 OHM JUMPER 1/16W 0402")
      (fields (field (name "POWER") "1/16W") (field (name "PART NUMBER") "RC0402JR-070RL"))
      (libsource (lib "*") (part "R0402_0R_5%"))
    )
    (comp (ref "U12")
      (value "TLV172IDCKT")
      (footprint "SC70-5_TLV172IDCKT")
      (description "IC OPAMP GP 1 CIRCUIT SC70-5")
      (fields
        (field (name "BANDWIDTH") "10 MHz")
        (field (name "MFG") "Texas Instruments")
        (field (name "VOLTAGE") "4.5V-36V")
      )
      (libsource (lib "*") (part "TLV172IDCKT"))
    )
    (comp (ref "U13")
      (value "AD7490SRUZ-EP")
      (footprint "TSSOP-28_AD7490SRUZ")
      (description "IC ADC 12BIT 1MSPS 16CH 28TSSOP")
      (fields
        (field (name "FSCLK") "20 MHz")
        (field (name "VOLTAGE") "2.7-5.25V")
        (field (name "PCBFOOTPRINT") "TSSOP-28")
        (field (name "PART NUMBER") "AD7490SRUZ-EP-RL7")
        (field (name "THROUGHPUT RATES") "1 MSPS")
        (field (name "RESOLUTION") "12-Bit")
        (field (name "VDD") "4.75-5.25V")
        (field (name "MFG") "Analog Devices Inc.")
      )
      (libsource (lib "*") (part "AD7490SRUZ-EP"))
    )
    (comp (ref "U14")
      (value "TLV172IDCKT")
      (footprint "SC70-5_TLV172IDCKT")
      (description "IC OPAMP GP 1 CIRCUIT SC70-5")
      (fields
        (field (name "BANDWIDTH") "10 MHz")
        (field (name "MFG") "Texas Instruments")
        (field (name "VOLTAGE") "4.5V-36V")
      )
      (libsource (lib "*") (part "TLV172IDCKT"))
    )
    (comp (ref "U15")
      (value "REF3325AIDCKT")
      (footprint "SC70-3_REF3320AIDCKR")
      (description "IC VREF SERIES 0.15% SC70-3")
      (fields
        (field (name "CURRENT") "5mA")
        (field (name "DEFINITION") "2.5V�0.15%")
        (field (name "MFG") "Texas Instruments")
        (field (name "VOLTAGE") "2.3V-5.5V")
      )
      (libsource (lib "*") (part "REF3325AIDCKT"))
    )
    (comp (ref "U16")
      (value "TLV172IDCKT")
      (footprint "SC70-5_TLV172IDCKT")
      (description "IC OPAMP GP 1 CIRCUIT SC70-5")
      (fields
        (field (name "BANDWIDTH") "10 MHz")
        (field (name "MFG") "Texas Instruments")
        (field (name "VOLTAGE") "4.5V-36V")
      )
      (libsource (lib "*") (part "TLV172IDCKT"))
    )
    (comp (ref "U17")
      (value "TLV172IDCKT")
      (footprint "SC70-5_TLV172IDCKT")
      (description "IC OPAMP GP 1 CIRCUIT SC70-5")
      (fields
        (field (name "BANDWIDTH") "10 MHz")
        (field (name "MFG") "Texas Instruments")
        (field (name "VOLTAGE") "4.5V-36V")
      )
      (libsource (lib "*") (part "TLV172IDCKT"))
    )
    (comp (ref "U18")
      (value "PDME1-S5-D5-S")
      (footprint "PDME1-S5-D5-S")
      (description "DC DC CONVERTER +/-5V 1W")
      (fields
        (field (name "POWER") "4.5-5.5V")
        (field (name "MFG") "CUI Inc.")
        (field (name "VOLTAGE") "5V/100mA")
      )
      (libsource (lib "*") (part "PDME1-S5-D5-S"))
    )
  )
  (nets
    (net (code "1") (name "+5VISO") (class "Default")
      (node (ref "C36") (pin "1") (pinfunction "1_1") (pintype "passive"))
      (node (ref "C53") (pin "1") (pinfunction "1_1") (pintype "passive"))
      (node (ref "C56") (pin "1") (pinfunction "1_1") (pintype "passive"))
      (node (ref "C57") (pin "1") (pinfunction "1_1") (pintype "passive"))
      (node (ref "L1") (pin "1") (pinfunction "1_1") (pintype "passive"))
      (node (ref "R100") (pin "1") (pinfunction "1_1") (pintype "passive"))
      (node (ref "R106") (pin "1") (pinfunction "1_1") (pintype "passive"))
      (node (ref "R60") (pin "1") (pinfunction "1_1") (pintype "passive"))
      (node (ref "R65") (pin "1") (pinfunction "1_1") (pintype "passive"))
      (node (ref "R71") (pin "1") (pinfunction "1_1") (pintype "passive"))
      (node (ref "R92") (pin "1") (pinfunction "1_1") (pintype "passive"))
      (node (ref "U13") (pin "22") (pinfunction "VDD_22") (pintype "power_in"))
      (node (ref "U18") (pin "6") (pinfunction "P_OUT_6") (pintype "open_collector"))
    )
    (net (code "2") (name "-5VISO") (class "Default")
      (node (ref "C55") (pin "2") (pinfunction "2_2") (pintype "passive"))
      (node (ref "R101") (pin "1") (pinfunction "1_1") (pintype "passive"))
      (node (ref "R105") (pin "1") (pinfunction "1_1") (pintype "passive"))
      (node (ref "R109") (pin "1") (pinfunction "1_1") (pintype "passive"))
      (node (ref "R63") (pin "1") (pinfunction "1_1") (pintype "passive"))
      (node (ref "R70") (pin "1") (pinfunction "1_1") (pintype "passive"))
      (node (ref "R85") (pin "1") (pinfunction "1_1") (pintype "passive"))
      (node (ref "U18") (pin "4") (pinfunction "N_OUT_4") (pintype "output"))
    )
    (net (code "3") (name "/-2V5") (class "Default")
      (node (ref "R102") (pin "1") (pinfunction "1_1") (pintype "passive"))
      (node (ref "R80") (pin "1") (pinfunction "1_1") (pintype "passive"))
      (node (ref "R98") (pin "1") (pinfunction "1_1") (pintype "passive"))
      (node (ref "U17") (pin "4") (pinfunction "OutPut_4") (pintype "open_collector"))
    )
    (net (code "4") (name "/2V5") (class "Default")
      (node (ref "C40") (pin "1") (pinfunction "1_1") (pintype "passive"))
      (node (ref "C41") (pin "1") (pinfunction "1_1") (pintype "passive"))
      (node (ref "R103") (pin "2") (pinfunction "2_2") (pintype "passive"))
      (node (ref "U13") (pin "23") (pinfunction "REFIN_23") (pintype "input"))
      (node (ref "U15") (pin "2") (pinfunction "OUT_2") (pintype "output"))
    )
    (net (code "5") (name "/A2D3V3") (class "Default")
      (node (ref "C32") (pin "1") (pinfunction "1_1") (pintype "passive"))
      (node (ref "R66") (pin "2") (pinfunction "2_2") (pintype "passive"))
      (node (ref "U13") (pin "10") (pinfunction "V_IN3_10") (pintype "input"))
    )
    (net (code "6") (name "/A2D_V_Bat") (class "Default")
      (node (ref "C33") (pin "1") (pinfunction "1_1") (pintype "passive"))
      (node (ref "R67") (pin "2") (pinfunction "2_2") (pintype "passive"))
      (node (ref "R73") (pin "1") (pinfunction "1_1") (pintype "passive"))
      (node (ref "U13") (pin "11") (pinfunction "V_IN2_11") (pintype "input"))
    )
    (net (code "7") (name "/A2D_V_Charge") (class "Default")
      (node (ref "C34") (pin "1") (pinfunction "1_1") (pintype "passive"))
      (node (ref "R68") (pin "2") (pinfunction "2_2") (pintype "passive"))
      (node (ref "R74") (pin "1") (pinfunction "1_1") (pintype "passive"))
      (node (ref "U13") (pin "12") (pinfunction "V_IN1_12") (pintype "input"))
    )
    (net (code "8") (name "/AudioIn") (class "Default")
      (node (ref "R84") (pin "1") (pinfunction "1_1") (pintype "passive"))
    )
    (net (code "9") (name "/AudioMic") (class "Default")
      (node (ref "R86") (pin "1") (pinfunction "1_1") (pintype "passive"))
    )
    (net (code "10") (name "/CSn") (class "Default")
      (node (ref "R104") (pin "2") (pinfunction "2_2") (pintype "passive"))
      (node (ref "U13") (pin "20") (pinfunction "~{CS}_20") (pintype "input"))
    )
    (net (code "11") (name "/DIN") (class "Default")
      (node (ref "U13") (pin "19") (pinfunction "DIN_19") (pintype "input"))
    )
    (net (code "12") (name "/DOUT") (class "Default")
      (node (ref "R107") (pin "2") (pinfunction "2_2") (pintype "passive"))
    )
    (net (code "13") (name "/GPS") (class "Default")
      (node (ref "R83") (pin "1") (pinfunction "1_1") (pintype "passive"))
    )
    (net (code "14") (name "/InPutBefore1275") (class "Default")
      (node (ref "R69") (pin "1") (pinfunction "1_1") (pintype "passive"))
    )
    (net (code "15") (name "/J+5V") (class "Default")
      (node (ref "C31") (pin "1") (pinfunction "1_1") (pintype "passive"))
      (node (ref "R65") (pin "2") (pinfunction "2_2") (pintype "passive"))
      (node (ref "R72") (pin "1") (pinfunction "1_1") (pintype "passive"))
      (node (ref "U13") (pin "9") (pinfunction "V_IN4_9") (pintype "input"))
    )
    (net (code "16") (name "/J-5V") (class "Default")
      (node (ref "C28") (pin "1") (pinfunction "1_1") (pintype "passive"))
      (node (ref "R61") (pin "2") (pinfunction "2_2") (pintype "passive"))
      (node (ref "R64") (pin "2") (pinfunction "2_2") (pintype "passive"))
      (node (ref "U13") (pin "8") (pinfunction "V_IN5_8") (pintype "input"))
    )
    (net (code "17") (name "/J-X") (class "Default")
      (node (ref "R78") (pin "1") (pinfunction "1_1") (pintype "passive"))
    )
    (net (code "18") (name "/J-Y") (class "Default")
      (node (ref "R97") (pin "1") (pinfunction "1_1") (pintype "passive"))
    )
    (net (code "19") (name "/J_X") (class "Default")
      (node (ref "C38") (pin "1") (pinfunction "1_1") (pintype "passive"))
      (node (ref "R76") (pin "2") (pinfunction "2_2") (pintype "passive"))
      (node (ref "R79") (pin "2") (pinfunction "2_2") (pintype "passive"))
      (node (ref "U13") (pin "7") (pinfunction "V_IN6_7") (pintype "input"))
    )
    (net (code "20") (name "/J_Y") (class "Default")
      (node (ref "R99") (pin "2") (pinfunction "2_2") (pintype "passive"))
      (node (ref "U13") (pin "6") (pinfunction "V_IN7_6") (pintype "input"))
    )
    (net (code "21") (name "/RS170") (class "Default")
      (node (ref "R81") (pin "1") (pinfunction "1_1") (pintype "passive"))
    )
    (net (code "22") (name "/RS422") (class "Default")
      (node (ref "R82") (pin "1") (pinfunction "1_1") (pintype "passive"))
    )
    (net (code "23") (name "/SCLK") (class "Default")
      (node (ref "U13") (pin "16") (pinfunction "SCLK_16") (pintype "input"))
    )
    (net (code "24") (name "/V_Bat") (class "Default")
      (node (ref "R67") (pin "1") (pinfunction "1_1") (pintype "passive"))
    )
    (net (code "25") (name "/V_Charge") (class "Default")
      (node (ref "R68") (pin "1") (pinfunction "1_1") (pintype "passive"))
    )
    (net (code "26") (name "3V3") (class "Default")
      (node (ref "C58") (pin "1") (pinfunction "1_1") (pintype "passive"))
      (node (ref "C59") (pin "1") (pinfunction "1_1") (pintype "passive"))
      (node (ref "R104") (pin "1") (pinfunction "1_1") (pintype "passive"))
      (node (ref "R66") (pin "1") (pinfunction "1_1") (pintype "passive"))
      (node (ref "U13") (pin "17") (pinfunction "VDRIVE_17") (pintype "power_in"))
    )
    (net (code "27") (name "5V") (class "Default")
      (node (ref "C54") (pin "1") (pinfunction "1_1") (pintype "passive"))
      (node (ref "U18") (pin "1") (pinfunction "VIN_1") (pintype "power_in"))
    )
    (net (code "28") (name "AGND") (class "Default")
      (node (ref "C27") (pin "2") (pinfunction "2_2") (pintype "passive"))
      (node (ref "C28") (pin "2") (pinfunction "2_2") (pintype "passive"))
      (node (ref "C29") (pin "2") (pinfunction "2_2") (pintype "passive"))
      (node (ref "C30") (pin "2") (pinfunction "2_2") (pintype "passive"))
      (node (ref "C31") (pin "2") (pinfunction "2_2") (pintype "passive"))
      (node (ref "C32") (pin "2") (pinfunction "2_2") (pintype "passive"))
      (node (ref "C33") (pin "2") (pinfunction "2_2") (pintype "passive"))
      (node (ref "C34") (pin "2") (pinfunction "2_2") (pintype "passive"))
      (node (ref "C35") (pin "2") (pinfunction "2_2") (pintype "passive"))
      (node (ref "C36") (pin "2") (pinfunction "2_2") (pintype "passive"))
      (node (ref "C37") (pin "2") (pinfunction "2_2") (pintype "passive"))
      (node (ref "C38") (pin "2") (pinfunction "2_2") (pintype "passive"))
      (node (ref "C39") (pin "2") (pinfunction "2_2") (pintype "passive"))
      (node (ref "C40") (pin "2") (pinfunction "2_2") (pintype "passive"))
      (node (ref "C41") (pin "2") (pinfunction "2_2") (pintype "passive"))
      (node (ref "C42") (pin "2") (pinfunction "2_2") (pintype "passive"))
      (node (ref "C43") (pin "1") (pinfunction "1_1") (pintype "passive"))
      (node (ref "C44") (pin "1") (pinfunction "1_1") (pintype "passive"))
      (node (ref "C45") (pin "1") (pinfunction "1_1") (pintype "passive"))
      (node (ref "C46") (pin "2") (pinfunction "2_2") (pintype "passive"))
      (node (ref "C47") (pin "1") (pinfunction "1_1") (pintype "passive"))
      (node (ref "C48") (pin "2") (pinfunction "2_2") (pintype "passive"))
      (node (ref "C49") (pin "1") (pinfunction "1_1") (pintype "passive"))
      (node (ref "C50") (pin "2") (pinfunction "2_2") (pintype "passive"))
      (node (ref "C51") (pin "1") (pinfunction "1_1") (pintype "passive"))
      (node (ref "C52") (pin "2") (pinfunction "2_2") (pintype "passive"))
      (node (ref "C56") (pin "2") (pinfunction "2_2") (pintype "passive"))
      (node (ref "C57") (pin "2") (pinfunction "2_2") (pintype "passive"))
      (node (ref "R108") (pin "1") (pinfunction "1_1") (pintype "passive"))
      (node (ref "R72") (pin "2") (pinfunction "2_2") (pintype "passive"))
      (node (ref "R73") (pin "2") (pinfunction "2_2") (pintype "passive"))
      (node (ref "R74") (pin "2") (pinfunction "2_2") (pintype "passive"))
      (node (ref "R75") (pin "2") (pinfunction "2_2") (pintype "passive"))
      (node (ref "R87") (pin "1") (pinfunction "1_1") (pintype "passive"))
      (node (ref "R88") (pin "1") (pinfunction "1_1") (pintype "passive"))
      (node (ref "R89") (pin "1") (pinfunction "1_1") (pintype "passive"))
      (node (ref "R90") (pin "1") (pinfunction "1_1") (pintype "passive"))
      (node (ref "R91") (pin "1") (pinfunction "1_1") (pintype "passive"))
      (node (ref "R93") (pin "1") (pinfunction "1_1") (pintype "passive"))
      (node (ref "U12") (pin "1") (pinfunction "+In_1") (pintype "input"))
      (node (ref "U13") (pin "14") (pinfunction "AGND1_14") (pintype "power_in"))
      (node (ref "U13") (pin "21") (pinfunction "AGND2_21") (pintype "power_in"))
      (node (ref "U13") (pin "24") (pinfunction "AGND3_24") (pintype "power_in"))
      (node (ref "U14") (pin "1") (pinfunction "+In_1") (pintype "input"))
      (node (ref "U15") (pin "3") (pinfunction "GND_3") (pintype "power_in"))
      (node (ref "U16") (pin "1") (pinfunction "+In_1") (pintype "input"))
      (node (ref "U17") (pin "1") (pinfunction "+In_1") (pintype "input"))
      (node (ref "U18") (pin "5") (pinfunction "0V_5") (pintype "input"))
    )
    (net (code "29") (name "GND") (class "Default")
      (node (ref "C54") (pin "2") (pinfunction "2_2") (pintype "passive"))
      (node (ref "C58") (pin "2") (pinfunction "2_2") (pintype "passive"))
      (node (ref "C59") (pin "2") (pinfunction "2_2") (pintype "passive"))
      (node (ref "R108") (pin "2") (pinfunction "2_2") (pintype "passive"))
      (node (ref "R110") (pin "2") (pinfunction "2_2") (pintype "passive"))
      (node (ref "R111") (pin "2") (pinfunction "2_2") (pintype "passive"))
      (node (ref "U18") (pin "2") (pinfunction "GND_2") (pintype "power_in"))
    )
    (net (code "30") (name "Net-(C46-Pad1)") (class "Default")
      (node (ref "C46") (pin "1") (pinfunction "1_1") (pintype "passive"))
      (node (ref "R94") (pin "2") (pinfunction "2_2") (pintype "passive"))
    )
    (net (code "31") (name "Net-(C53-Pad2)") (class "Default")
      (node (ref "C53") (pin "2") (pinfunction "2_2") (pintype "passive"))
      (node (ref "C55") (pin "1") (pinfunction "1_1") (pintype "passive"))
    )
    (net (code "32") (name "Net-(D8-C)") (class "Default")
      (node (ref "D8") (pin "1") (pinfunction "C_1") (pintype "passive"))
      (node (ref "R109") (pin "2") (pinfunction "2_2") (pintype "passive"))
    )
    (net (code "33") (name "Net-(ICT1-Pad1)") (class "Default")
      (node (ref "ICT1") (pin "1") (pinfunction "1_1") (pintype "passive"))
      (node (ref "R95") (pin "1") (pinfunction "1_1") (pintype "passive"))
    )
    (net (code "34") (name "Net-(R76-Pad1)") (class "Default")
      (node (ref "R76") (pin "1") (pinfunction "1_1") (pintype "passive"))
      (node (ref "R77") (pin "1") (pinfunction "1_1") (pintype "passive"))
      (node (ref "R80") (pin "2") (pinfunction "2_2") (pintype "passive"))
    )
    (net (code "35") (name "Net-(R94-Pad1)") (class "Default")
      (node (ref "R94") (pin "1") (pinfunction "1_1") (pintype "passive"))
      (node (ref "R96") (pin "1") (pinfunction "1_1") (pintype "passive"))
      (node (ref "R98") (pin "2") (pinfunction "2_2") (pintype "passive"))
    )
    (net (code "36") (name "Net-(U12-+V)") (class "Default")
      (node (ref "C27") (pin "1") (pinfunction "1_1") (pintype "passive"))
      (node (ref "R60") (pin "2") (pinfunction "2_2") (pintype "passive"))
      (node (ref "U12") (pin "5") (pinfunction "+V_5") (pintype "power_in"))
    )
    (net (code "37") (name "Net-(U12--In)") (class "Default")
      (node (ref "R61") (pin "1") (pinfunction "1_1") (pintype "passive"))
      (node (ref "R62") (pin "1") (pinfunction "1_1") (pintype "passive"))
      (node (ref "R63") (pin "2") (pinfunction "2_2") (pintype "passive"))
      (node (ref "U12") (pin "3") (pinfunction "-In_3") (pintype "input"))
    )
    (net (code "38") (name "Net-(U12--V)") (class "Default")
      (node (ref "C29") (pin "1") (pinfunction "1_1") (pintype "passive"))
      (node (ref "R70") (pin "2") (pinfunction "2_2") (pintype "passive"))
      (node (ref "U12") (pin "2") (pinfunction "-V_2") (pintype "power_in"))
    )
    (net (code "39") (name "Net-(U12-OutPut)") (class "Default")
      (node (ref "R62") (pin "2") (pinfunction "2_2") (pintype "passive"))
      (node (ref "R64") (pin "1") (pinfunction "1_1") (pintype "passive"))
      (node (ref "U12") (pin "4") (pinfunction "OutPut_4") (pintype "open_collector"))
    )
    (net (code "40") (name "Net-(U13A-V_IN0)") (class "Default")
      (node (ref "C35") (pin "1") (pinfunction "1_1") (pintype "passive"))
      (node (ref "R69") (pin "2") (pinfunction "2_2") (pintype "passive"))
      (node (ref "R75") (pin "1") (pinfunction "1_1") (pintype "passive"))
      (node (ref "U13") (pin "13") (pinfunction "V_IN0_13") (pintype "input"))
    )
    (net (code "41") (name "Net-(U13A-V_IN8)") (class "Default")
      (node (ref "C49") (pin "2") (pinfunction "2_2") (pintype "passive"))
      (node (ref "R81") (pin "2") (pinfunction "2_2") (pintype "passive"))
      (node (ref "R91") (pin "2") (pinfunction "2_2") (pintype "passive"))
      (node (ref "U13") (pin "5") (pinfunction "V_IN8_5") (pintype "input"))
    )
    (net (code "42") (name "Net-(U13A-V_IN9)") (class "Default")
      (node (ref "C47") (pin "2") (pinfunction "2_2") (pintype "passive"))
      (node (ref "R82") (pin "2") (pinfunction "2_2") (pintype "passive"))
      (node (ref "R90") (pin "2") (pinfunction "2_2") (pintype "passive"))
      (node (ref "U13") (pin "3") (pinfunction "V_IN9_3") (pintype "input"))
    )
    (net (code "43") (name "Net-(U13A-V_IN10)") (class "Default")
      (node (ref "C45") (pin "2") (pinfunction "2_2") (pintype "passive"))
      (node (ref "R83") (pin "2") (pinfunction "2_2") (pintype "passive"))
      (node (ref "R89") (pin "2") (pinfunction "2_2") (pintype "passive"))
      (node (ref "U13") (pin "2") (pinfunction "V_IN10_2") (pintype "input"))
    )
    (net (code "44") (name "Net-(U13A-V_IN11)") (class "Default")
      (node (ref "C43") (pin "2") (pinfunction "2_2") (pintype "passive"))
      (node (ref "R84") (pin "2") (pinfunction "2_2") (pintype "passive"))
      (node (ref "R88") (pin "2") (pinfunction "2_2") (pintype "passive"))
      (node (ref "U13") (pin "1") (pinfunction "V_IN11_1") (pintype "input"))
    )
    (net (code "45") (name "Net-(U13A-V_IN12)") (class "Default")
      (node (ref "C44") (pin "2") (pinfunction "2_2") (pintype "passive"))
      (node (ref "R86") (pin "2") (pinfunction "2_2") (pintype "passive"))
      (node (ref "R87") (pin "2") (pinfunction "2_2") (pintype "passive"))
      (node (ref "U13") (pin "28") (pinfunction "V_IN12_28") (pintype "input"))
    )
    (net (code "46") (name "Net-(U13A-V_IN15)") (class "Default")
      (node (ref "C51") (pin "2") (pinfunction "2_2") (pintype "passive"))
      (node (ref "R93") (pin "2") (pinfunction "2_2") (pintype "passive"))
      (node (ref "R95") (pin "2") (pinfunction "2_2") (pintype "passive"))
      (node (ref "U13") (pin "25") (pinfunction "V_IN15_25") (pintype "input"))
    )
    (net (code "47") (name "Net-(U13B-DOUT)") (class "Default")
      (node (ref "R107") (pin "1") (pinfunction "1_1") (pintype "passive"))
      (node (ref "U13") (pin "15") (pinfunction "DOUT_15") (pintype "output"))
    )
    (net (code "48") (name "Net-(U13C-NC1)") (class "Default")
      (node (ref "R110") (pin "1") (pinfunction "1_1") (pintype "passive"))
      (node (ref "U13") (pin "18") (pinfunction "NC1_18") (pintype "passive"))
    )
    (net (code "49") (name "Net-(U13C-NC2)") (class "Default")
      (node (ref "R111") (pin "1") (pinfunction "1_1") (pintype "passive"))
      (node (ref "U13") (pin "4") (pinfunction "NC2_4") (pintype "passive"))
    )
    (net (code "50") (name "Net-(U14-+V)") (class "Default")
      (node (ref "C30") (pin "1") (pinfunction "1_1") (pintype "passive"))
      (node (ref "R71") (pin "2") (pinfunction "2_2") (pintype "passive"))
      (node (ref "U14") (pin "5") (pinfunction "+V_5") (pintype "power_in"))
    )
    (net (code "51") (name "Net-(U14--In)") (class "Default")
      (node (ref "R78") (pin "2") (pinfunction "2_2") (pintype "passive"))
      (node (ref "U14") (pin "3") (pinfunction "-In_3") (pintype "input"))
    )
    (net (code "52") (name "Net-(U14--V)") (class "Default")
      (node (ref "C39") (pin "1") (pinfunction "1_1") (pintype "passive"))
      (node (ref "R85") (pin "2") (pinfunction "2_2") (pintype "passive"))
      (node (ref "U14") (pin "2") (pinfunction "-V_2") (pintype "power_in"))
    )
    (net (code "53") (name "Net-(U14-OutPut)") (class "Default")
      (node (ref "R77") (pin "2") (pinfunction "2_2") (pintype "passive"))
      (node (ref "R79") (pin "1") (pinfunction "1_1") (pintype "passive"))
      (node (ref "U14") (pin "4") (pinfunction "OutPut_4") (pintype "open_collector"))
    )
    (net (code "54") (name "Net-(U15-IN)") (class "Default")
      (node (ref "C37") (pin "1") (pinfunction "1_1") (pintype "passive"))
      (node (ref "L1") (pin "2") (pinfunction "2_2") (pintype "passive"))
      (node (ref "U15") (pin "1") (pinfunction "IN_1") (pintype "power_in"))
    )
    (net (code "55") (name "Net-(U16-+V)") (class "Default")
      (node (ref "C42") (pin "1") (pinfunction "1_1") (pintype "passive"))
      (node (ref "R92") (pin "2") (pinfunction "2_2") (pintype "passive"))
      (node (ref "U16") (pin "5") (pinfunction "+V_5") (pintype "power_in"))
    )
    (net (code "56") (name "Net-(U16--In)") (class "Default")
      (node (ref "R97") (pin "2") (pinfunction "2_2") (pintype "passive"))
      (node (ref "U16") (pin "3") (pinfunction "-In_3") (pintype "input"))
    )
    (net (code "57") (name "Net-(U16--V)") (class "Default")
      (node (ref "C50") (pin "1") (pinfunction "1_1") (pintype "passive"))
      (node (ref "R101") (pin "2") (pinfunction "2_2") (pintype "passive"))
      (node (ref "U16") (pin "2") (pinfunction "-V_2") (pintype "power_in"))
    )
    (net (code "58") (name "Net-(U16-OutPut)") (class "Default")
      (node (ref "R96") (pin "2") (pinfunction "2_2") (pintype "passive"))
      (node (ref "R99") (pin "1") (pinfunction "1_1") (pintype "passive"))
      (node (ref "U16") (pin "4") (pinfunction "OutPut_4") (pintype "open_collector"))
    )
    (net (code "59") (name "Net-(U17-+V)") (class "Default")
      (node (ref "C48") (pin "1") (pinfunction "1_1") (pintype "passive"))
      (node (ref "R100") (pin "2") (pinfunction "2_2") (pintype "passive"))
      (node (ref "U17") (pin "5") (pinfunction "+V_5") (pintype "power_in"))
    )
    (net (code "60") (name "Net-(U17--In)") (class "Default")
      (node (ref "R102") (pin "2") (pinfunction "2_2") (pintype "passive"))
      (node (ref "R103") (pin "1") (pinfunction "1_1") (pintype "passive"))
      (node (ref "U17") (pin "3") (pinfunction "-In_3") (pintype "input"))
    )
    (net (code "61") (name "Net-(U17--V)") (class "Default")
      (node (ref "C52") (pin "1") (pinfunction "1_1") (pintype "passive"))
      (node (ref "R105") (pin "2") (pinfunction "2_2") (pintype "passive"))
      (node (ref "U17") (pin "2") (pinfunction "-V_2") (pintype "power_in"))
    )
    (net (code "62") (name "unconnected-(D7-A-Pad2)") (class "Default")
      (node (ref "D7") (pin "2") (pinfunction "A_2") (pintype "passive+no_connect"))
    )
    (net (code "63") (name "unconnected-(D7-C-Pad1)") (class "Default")
      (node (ref "D7") (pin "1") (pinfunction "C_1") (pintype "passive+no_connect"))
    )
    (net (code "64") (name "unconnected-(D8-A-Pad2)") (class "Default")
      (node (ref "D8") (pin "2") (pinfunction "A_2") (pintype "passive"))
    )
    (net (code "65") (name "unconnected-(R106-Pad2)") (class "Default")
      (node (ref "R106") (pin "2") (pinfunction "2_2") (pintype "passive"))
    )
    (net (code "66") (name "unconnected-(U13A-V_IN13-Pad27)") (class "Default")
      (node (ref "U13") (pin "27") (pinfunction "V_IN13_27") (pintype "input+no_connect"))
    )
    (net (code "67") (name "unconnected-(U13A-V_IN14-Pad26)") (class "Default")
      (node (ref "U13") (pin "26") (pinfunction "V_IN14_26") (pintype "input+no_connect"))
    )
  )
)
